# Chassis924.net
KiCad netlist of a schematic drawn in EasyEDA Pro
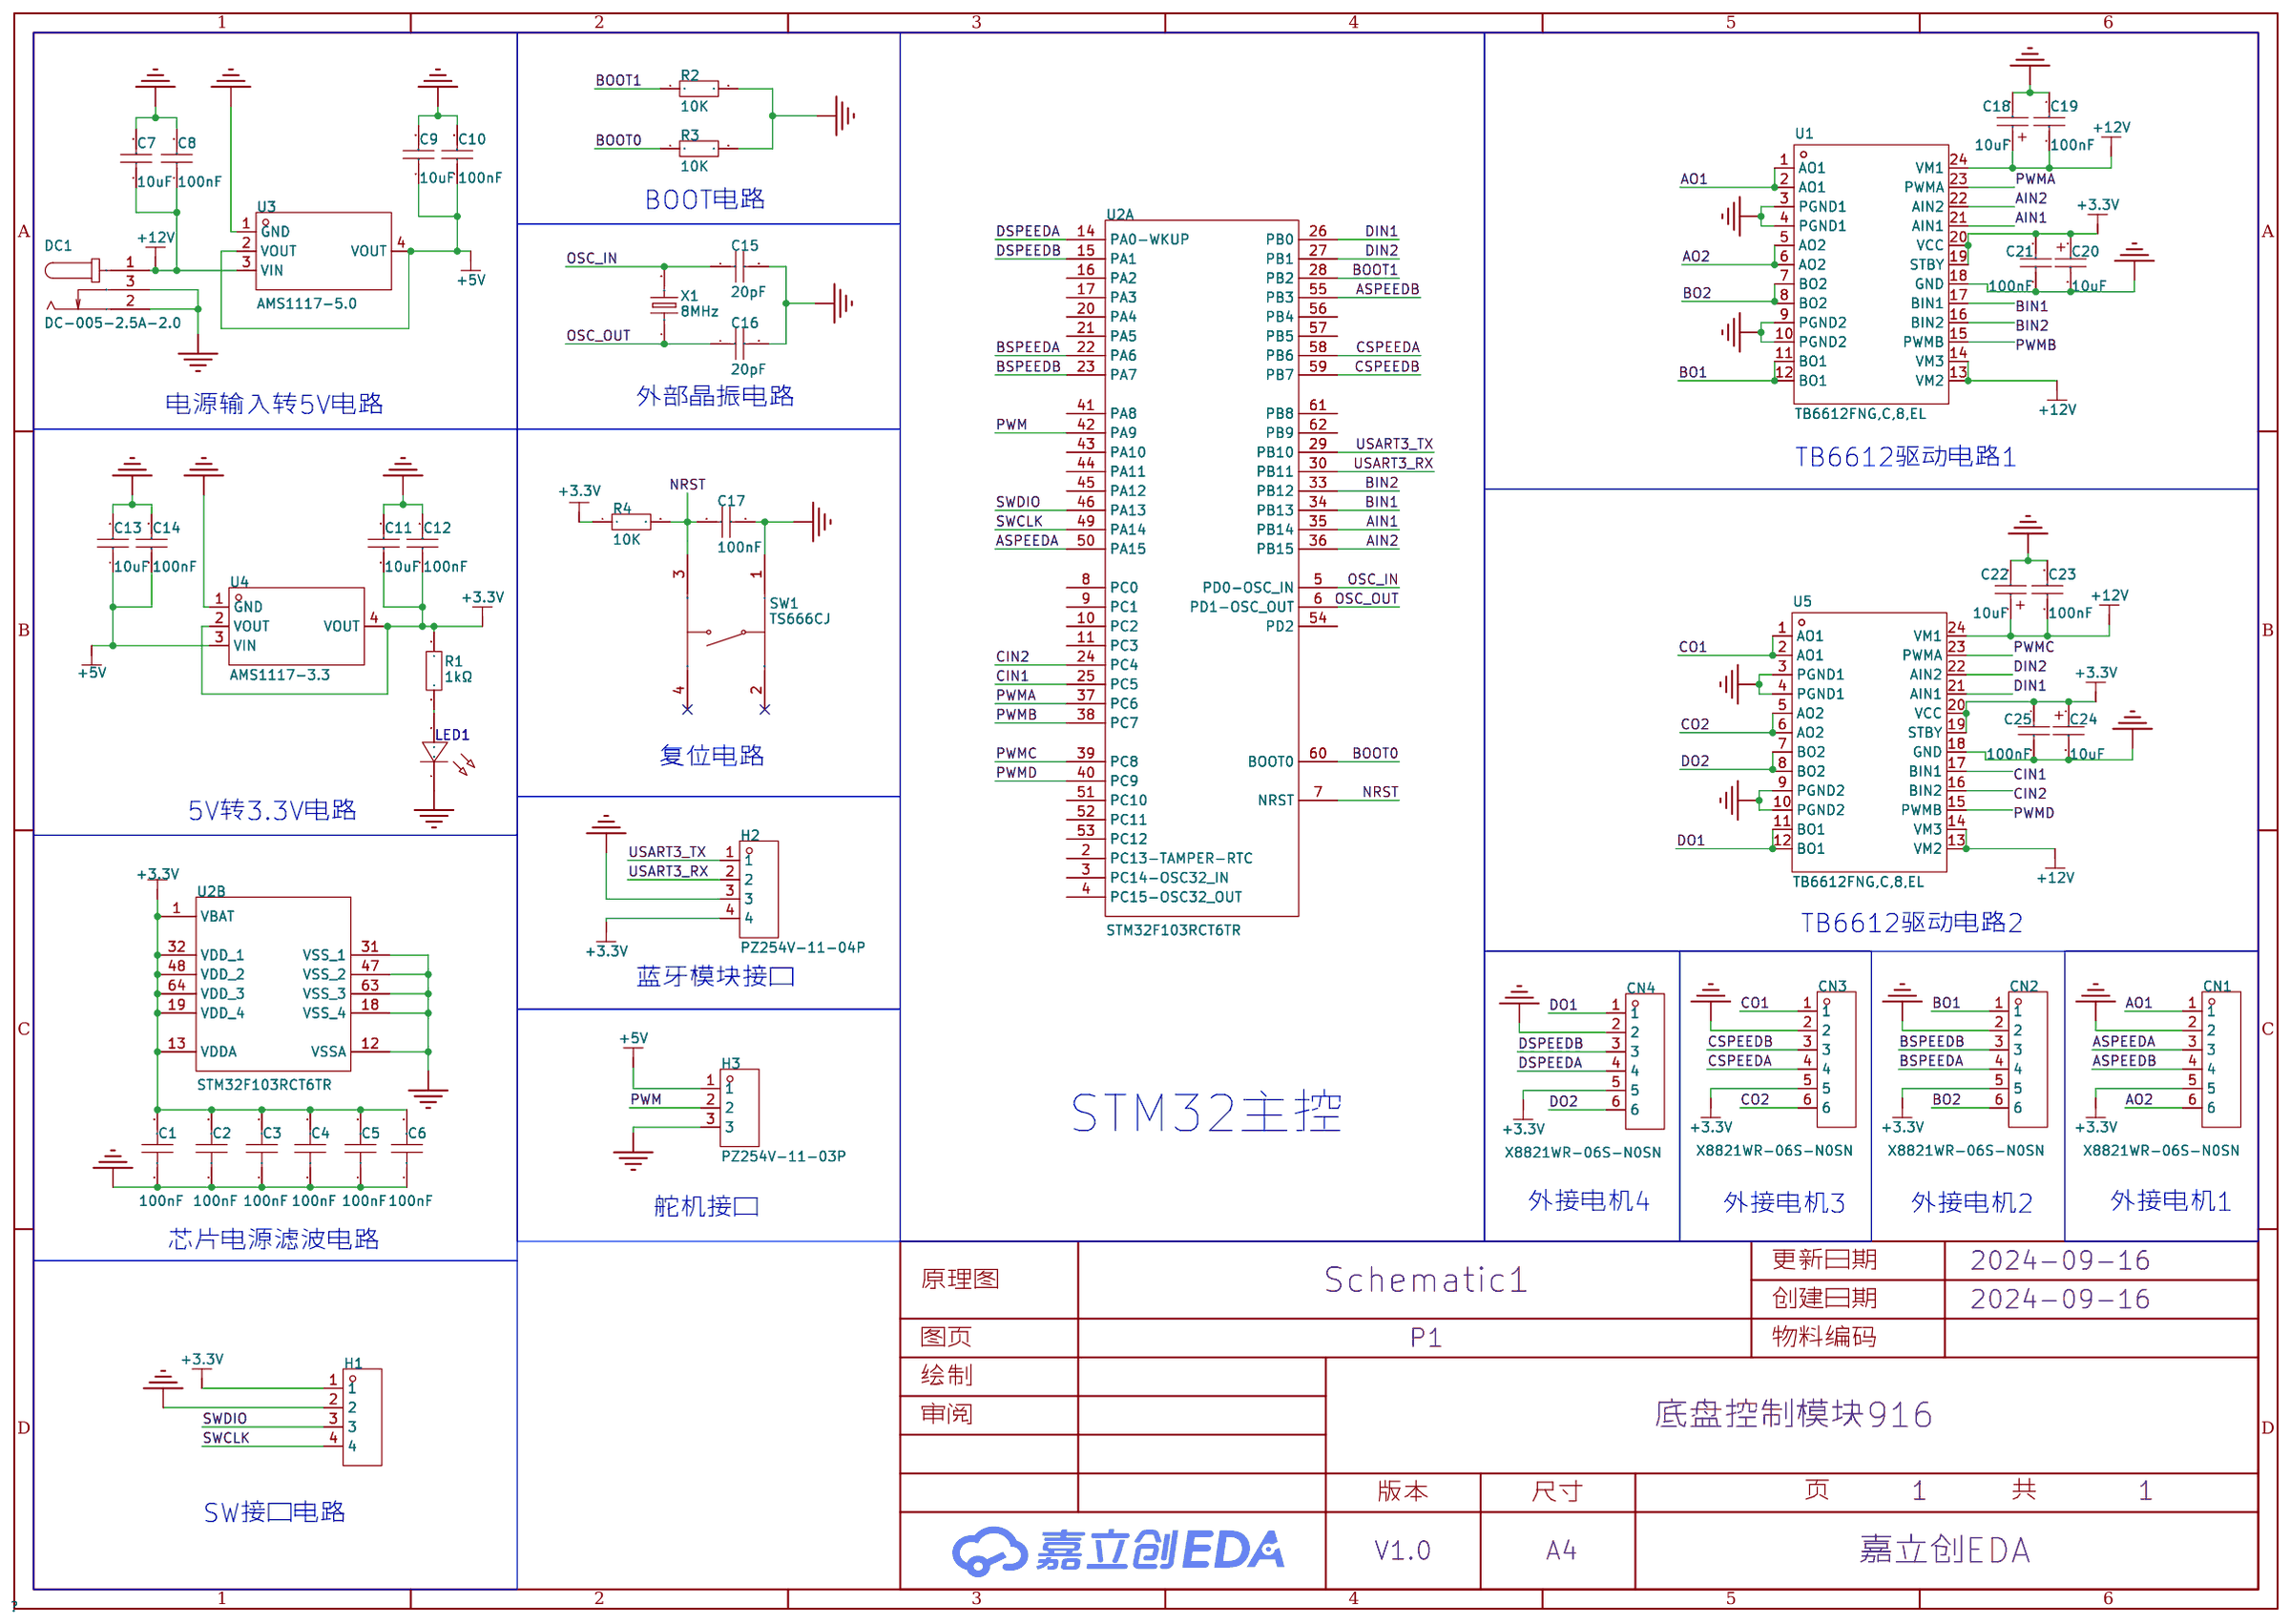
[diagram p0: schematic sheet]

(export (version "E")
  (design (tool "Eeschema 10.0.6"))
  (components
    (comp (ref "C1")
      (value "100nF")
      (footprint "easyedapro:C0603")
      (libsource (lib "easyedapro") (part "CapAcitance"))
    )
    (comp (ref "C2")
      (value "100nF")
      (footprint "easyedapro:C0603")
      (libsource (lib "easyedapro") (part "CapAcitance"))
    )
    (comp (ref "C3")
      (value "100nF")
      (footprint "easyedapro:C0603")
      (libsource (lib "easyedapro") (part "CapAcitance"))
    )
    (comp (ref "C4")
      (value "100nF")
      (footprint "easyedapro:C0603")
      (libsource (lib "easyedapro") (part "CapAcitance"))
    )
    (comp (ref "C5")
      (value "100nF")
      (footprint "easyedapro:C0603")
      (libsource (lib "easyedapro") (part "CapAcitance"))
    )
    (comp (ref "C6")
      (value "100nF")
      (footprint "easyedapro:C0603")
      (libsource (lib "easyedapro") (part "CapAcitance"))
    )
    (comp (ref "C7")
      (value "10uF")
      (footprint "easyedapro:C0402")
      (description "容值:10uF;精度:±20%;额定电压:6.3V;材质(温度系数):X5R;")
      (fields
        (field (name "Manufacturer Part") "CL05A106MQ5NUNC")
        (field (name "Manufacturer") "SAMSUNG(三星)")
      )
      (libsource (lib "easyedapro") (part "CL05A106MQ5NUNC"))
    )
    (comp (ref "C8")
      (value "100nF")
      (footprint "easyedapro:C0402")
      (description "容值:100nF;精度:±10%;额定电压:16V;材质(温度系数):X7R;")
      (fields
        (field (name "Manufacturer Part") "CL05B104KO5NNNC")
        (field (name "Manufacturer") "SAMSUNG(三星)")
      )
      (libsource (lib "easyedapro") (part "CL05B104KO5NNNC"))
    )
    (comp (ref "C9")
      (value "10uF")
      (footprint "easyedapro:C0402")
      (description "容值:10uF;精度:±20%;额定电压:6.3V;材质(温度系数):X5R;")
      (fields
        (field (name "Manufacturer Part") "CL05A106MQ5NUNC")
        (field (name "Manufacturer") "SAMSUNG(三星)")
      )
      (libsource (lib "easyedapro") (part "CL05A106MQ5NUNC"))
    )
    (comp (ref "C10")
      (value "100nF")
      (footprint "easyedapro:C0402")
      (description "容值:100nF;精度:±10%;额定电压:16V;材质(温度系数):X7R;")
      (fields
        (field (name "Manufacturer Part") "CL05B104KO5NNNC")
        (field (name "Manufacturer") "SAMSUNG(三星)")
      )
      (libsource (lib "easyedapro") (part "CL05B104KO5NNNC"))
    )
    (comp (ref "C11")
      (value "10uF")
      (footprint "easyedapro:C0402")
      (description "容值:10uF;精度:±20%;额定电压:6.3V;材质(温度系数):X5R;")
      (fields
        (field (name "Manufacturer Part") "CL05A106MQ5NUNC")
        (field (name "Manufacturer") "SAMSUNG(三星)")
      )
      (libsource (lib "easyedapro") (part "CL05A106MQ5NUNC"))
    )
    (comp (ref "C12")
      (value "100nF")
      (footprint "easyedapro:C0402")
      (description "容值:100nF;精度:±10%;额定电压:16V;材质(温度系数):X7R;")
      (fields
        (field (name "Manufacturer Part") "CL05B104KO5NNNC")
        (field (name "Manufacturer") "SAMSUNG(三星)")
      )
      (libsource (lib "easyedapro") (part "CL05B104KO5NNNC"))
    )
    (comp (ref "C13")
      (value "10uF")
      (footprint "easyedapro:C0402")
      (description "容值:10uF;精度:±20%;额定电压:6.3V;材质(温度系数):X5R;")
      (fields
        (field (name "Manufacturer Part") "CL05A106MQ5NUNC")
        (field (name "Manufacturer") "SAMSUNG(三星)")
      )
      (libsource (lib "easyedapro") (part "CL05A106MQ5NUNC"))
    )
    (comp (ref "C14")
      (value "100nF")
      (footprint "easyedapro:C0402")
      (description "容值:100nF;精度:±10%;额定电压:16V;材质(温度系数):X7R;")
      (fields
        (field (name "Manufacturer Part") "CL05B104KO5NNNC")
        (field (name "Manufacturer") "SAMSUNG(三星)")
      )
      (libsource (lib "easyedapro") (part "CL05B104KO5NNNC"))
    )
    (comp (ref "C15")
      (value "20pF")
      (footprint "easyedapro:C0402")
      (description "容值:20pF;精度:±5%;额定电压:50V;材质(温度系数):C0G;")
      (fields (field (name "Manufacturer Part") "0402CG200J500NT") (field (name "Manufacturer") "FH(风华)"))
      (libsource (lib "easyedapro") (part "0402CG200J500NT"))
    )
    (comp (ref "C16")
      (value "20pF")
      (footprint "easyedapro:C0402")
      (description "容值:20pF;精度:±5%;额定电压:50V;材质(温度系数):C0G;")
      (fields (field (name "Manufacturer Part") "0402CG200J500NT") (field (name "Manufacturer") "FH(风华)"))
      (libsource (lib "easyedapro") (part "0402CG200J500NT"))
    )
    (comp (ref "C17")
      (value "100nF")
      (footprint "easyedapro:C0402")
      (description "容值:100nF;精度:±10%;额定电压:16V;材质(温度系数):X7R;")
      (fields
        (field (name "Manufacturer Part") "CL05B104KO5NNNC")
        (field (name "Manufacturer") "SAMSUNG(三星)")
      )
      (libsource (lib "easyedapro") (part "CL05B104KO5NNNC"))
    )
    (comp (ref "C18")
      (value "10uF")
      (footprint "easyedapro:CAP-SMD_L3.2-W1.6-RD-C7171")
      (description "容值:10uF;精度:±10%;额定电压:16V;等效串联电阻:3Ω@100kHz;")
      (fields (field (name "Manufacturer Part") "TAJA106K016RNJ") (field (name "Manufacturer") "Kyocera AVX"))
      (libsource (lib "easyedapro") (part "TAJA106K016RNJ"))
    )
    (comp (ref "C19")
      (value "100nF")
      (footprint "easyedapro:C0402")
      (description "容值:100nF;精度:±10%;额定电压:16V;材质(温度系数):X7R;")
      (fields
        (field (name "Manufacturer Part") "CL05B104KO5NNNC")
        (field (name "Manufacturer") "SAMSUNG(三星)")
      )
      (libsource (lib "easyedapro") (part "CL05B104KO5NNNC"))
    )
    (comp (ref "C20")
      (value "10uF")
      (footprint "easyedapro:CAP-SMD_L3.2-W1.6-RD-C7171")
      (description "容值:10uF;精度:±10%;额定电压:16V;等效串联电阻:3Ω@100kHz;")
      (fields (field (name "Manufacturer Part") "TAJA106K016RNJ") (field (name "Manufacturer") "Kyocera AVX"))
      (libsource (lib "easyedapro") (part "TAJA106K016RNJ"))
    )
    (comp (ref "C21")
      (value "100nF")
      (footprint "easyedapro:C0402")
      (description "容值:100nF;精度:±10%;额定电压:16V;材质(温度系数):X7R;")
      (fields
        (field (name "Manufacturer Part") "CL05B104KO5NNNC")
        (field (name "Manufacturer") "SAMSUNG(三星)")
      )
      (libsource (lib "easyedapro") (part "CL05B104KO5NNNC"))
    )
    (comp (ref "C22")
      (value "10uF")
      (footprint "easyedapro:CAP-SMD_L3.2-W1.6-RD-C7171")
      (description "容值:10uF;精度:±10%;额定电压:16V;等效串联电阻:3Ω@100kHz;")
      (fields (field (name "Manufacturer Part") "TAJA106K016RNJ") (field (name "Manufacturer") "Kyocera AVX"))
      (libsource (lib "easyedapro") (part "TAJA106K016RNJ"))
    )
    (comp (ref "C23")
      (value "100nF")
      (footprint "easyedapro:C0402")
      (description "容值:100nF;精度:±10%;额定电压:16V;材质(温度系数):X7R;")
      (fields
        (field (name "Manufacturer Part") "CL05B104KO5NNNC")
        (field (name "Manufacturer") "SAMSUNG(三星)")
      )
      (libsource (lib "easyedapro") (part "CL05B104KO5NNNC"))
    )
    (comp (ref "C24")
      (value "10uF")
      (footprint "easyedapro:CAP-SMD_L3.2-W1.6-RD-C7171")
      (description "容值:10uF;精度:±10%;额定电压:16V;等效串联电阻:3Ω@100kHz;")
      (fields (field (name "Manufacturer Part") "TAJA106K016RNJ") (field (name "Manufacturer") "Kyocera AVX"))
      (libsource (lib "easyedapro") (part "TAJA106K016RNJ"))
    )
    (comp (ref "C25")
      (value "100nF")
      (footprint "easyedapro:C0402")
      (description "容值:100nF;精度:±10%;额定电压:16V;材质(温度系数):X7R;")
      (fields
        (field (name "Manufacturer Part") "CL05B104KO5NNNC")
        (field (name "Manufacturer") "SAMSUNG(三星)")
      )
      (libsource (lib "easyedapro") (part "CL05B104KO5NNNC"))
    )
    (comp (ref "CN1")
      (value "X8821WR-06S-N0SN")
      (footprint "easyedapro:CONN-TH_6P-P2.50_X8821WR-06S-N2SN")
      (description "插针结构:1x6P;间距:2.5mm;安装方式:弯插;参考系列:XH;总PIN数:6P;排数:1;每排PIN数:6;行距:-;额定电流:3A;触头材质:黄铜;触头镀层:锡;工作温度范围:-;")
      (fields (field (name "Manufacturer") "XKB Connection(中国星坤)"))
      (libsource (lib "easyedapro") (part "X8821WR-06S-N0SN"))
    )
    (comp (ref "CN2")
      (value "X8821WR-06S-N0SN")
      (footprint "easyedapro:CONN-TH_6P-P2.50_X8821WR-06S-N2SN")
      (description "插针结构:1x6P;间距:2.5mm;安装方式:弯插;参考系列:XH;总PIN数:6P;排数:1;每排PIN数:6;行距:-;额定电流:3A;触头材质:黄铜;触头镀层:锡;工作温度范围:-;")
      (fields (field (name "Manufacturer") "XKB Connection(中国星坤)"))
      (libsource (lib "easyedapro") (part "X8821WR-06S-N0SN"))
    )
    (comp (ref "CN3")
      (value "X8821WR-06S-N0SN")
      (footprint "easyedapro:CONN-TH_6P-P2.50_X8821WR-06S-N2SN")
      (description "插针结构:1x6P;间距:2.5mm;安装方式:弯插;参考系列:XH;总PIN数:6P;排数:1;每排PIN数:6;行距:-;额定电流:3A;触头材质:黄铜;触头镀层:锡;工作温度范围:-;")
      (fields (field (name "Manufacturer") "XKB Connection(中国星坤)"))
      (libsource (lib "easyedapro") (part "X8821WR-06S-N0SN"))
    )
    (comp (ref "CN4")
      (value "X8821WR-06S-N0SN")
      (footprint "easyedapro:CONN-TH_6P-P2.50_X8821WR-06S-N2SN")
      (description "插针结构:1x6P;间距:2.5mm;安装方式:弯插;参考系列:XH;总PIN数:6P;排数:1;每排PIN数:6;行距:-;额定电流:3A;触头材质:黄铜;触头镀层:锡;工作温度范围:-;")
      (fields (field (name "Manufacturer") "XKB Connection(中国星坤)"))
      (libsource (lib "easyedapro") (part "X8821WR-06S-N0SN"))
    )
    (comp (ref "DC1")
      (value "DC-005-2.5A-2.0")
      (footprint "easyedapro:CONN-TH_DC-005-2.5A-2.0")
      (fields (field (name "Manufacturer") "XKB Connection(中国星坤)"))
      (libsource (lib "easyedapro") (part "DC-005-2.5A-2.0"))
    )
    (comp (ref "H1")
      (value "~")
      (footprint "easyedapro:HDR-TH_4P-P2.54-V-M")
      (libsource (lib "easyedapro") (part "PZ254V-11-04P"))
    )
    (comp (ref "H2")
      (value "PZ254V-11-04P")
      (footprint "easyedapro:HDR-TH_4P-P2.54-V-M")
      (fields (field (name "Manufacturer") "XFCN(兴飞)"))
      (libsource (lib "easyedapro") (part "PZ254V-11-04P_C2691448"))
    )
    (comp (ref "H3")
      (value "PZ254V-11-03P")
      (footprint "easyedapro:HDR-TH_3P-P2.54-V-M")
      (fields (field (name "Manufacturer") "XFCN(兴飞)"))
      (libsource (lib "easyedapro") (part "PZ254V-11-03P_C2937625"))
    )
    (comp (ref "LED1")
      (value "~")
      (footprint "easyedapro:LED_0805")
      (libsource (lib "easyedapro") (part "LED_B"))
    )
    (comp (ref "R1")
      (value "1kΩ")
      (footprint "easyedapro:R0603")
      (description "电阻类型:厚膜电阻;阻值:1kΩ;精度:±1%;功率:100mW;最大工作电压:75V;温度系数:±100ppm/°C;")
      (fields
        (field (name "Manufacturer Part") "0603WAF1001T5E")
        (field (name "Manufacturer") "UNI-ROYAL(厚声)")
      )
      (libsource (lib "easyedapro") (part "0603WAF1001T5E"))
    )
    (comp (ref "R2") (value "10K") (footprint "easyedapro:R0603") (libsource (lib "easyedapro") (part "电阻")))
    (comp (ref "R3") (value "10K") (footprint "easyedapro:R0603") (libsource (lib "easyedapro") (part "电阻")))
    (comp (ref "R4") (value "10K") (footprint "easyedapro:R0603") (libsource (lib "easyedapro") (part "电阻")))
    (comp (ref "SW1")
      (value "TS666CJ")
      (footprint "easyedapro:SW-TH_4P-L6.0-W6.0-P4.50-LS6.5")
      (fields (field (name "Manufacturer") "SHOU HAN(首韩)"))
      (libsource (lib "easyedapro") (part "TS666CJ"))
    )
    (comp (ref "U1")
      (value "TB6612FNG,C,8,EL")
      (footprint "easyedapro:SSOP-24_L8.3-W5.6-P0.65-LS7.6-BL")
      (fields (field (name "Manufacturer") "TOSHIBA(东芝)"))
      (libsource (lib "easyedapro") (part "TB6612FNG,C,8,EL"))
    )
    (comp (ref "U2")
      (value "STM32F103RCT6TR")
      (footprint "easyedapro:LQFP-64_L10.0-W10.0-P0.50-LS12.0-BL")
      (description "CPU内核:ARM-M3;程序存储容量:256KB;RAM总容量:48KB;GPIO端口数量:51;工作电压范围:2V~3.6V;CPU最大主频:72MHz;程序存储器类型:FLASH;")
      (fields (field (name "Manufacturer") "ST(意法半导体)"))
      (libsource (lib "easyedapro") (part "STM32F103RCT6TR"))
    )
    (comp (ref "U3")
      (value "AMS1117-5.0")
      (footprint "easyedapro:SOT-223_L6.5-W3.5-P2.30-LS7.0-BR")
      (description "输出类型:固定;最大输入电压:12V;输出电压:5V;最大输出电流:1A;电源纹波抑制比(PSRR):68dB@(120Hz);输出极性:正极;")
      (fields (field (name "Manufacturer") "AMS"))
      (libsource (lib "easyedapro") (part "AMS1117-5.0"))
    )
    (comp (ref "U4")
      (value "AMS1117-3.3")
      (footprint "easyedapro:SOT-223-3_L6.5-W3.4-P2.30-LS7.0-BR")
      (description "输出类型:固定;最大输入电压:-;输出电压:3.3V;最大输出电流:1A;电源纹波抑制比(PSRR):72dB@(120Hz);输出极性:正极;")
      (fields (field (name "Manufacturer") "AMS"))
      (libsource (lib "easyedapro") (part "AMS1117-3.3"))
    )
    (comp (ref "U5")
      (value "TB6612FNG,C,8,EL")
      (footprint "easyedapro:SSOP-24_L8.3-W5.6-P0.65-LS7.6-BL")
      (fields (field (name "Manufacturer") "TOSHIBA(东芝)"))
      (libsource (lib "easyedapro") (part "TB6612FNG,C,8,EL"))
    )
    (comp (ref "X1")
      (value "8MHz")
      (footprint "easyedapro:HC-49US_L11.5-W4.5-P4.88")
      (description "晶振类型:直插晶振;频率:8MHz;常温频差:±20ppm;外接负载电容:20pF;频率稳定度(全温):±20ppm;")
      (fields
        (field (name "Manufacturer Part") "49S-8.000-20-20-20/A")
        (field (name "Manufacturer") "LIMING(利明)")
      )
      (libsource (lib "easyedapro") (part "49S-8.000-20-20-20/A"))
    )
  )
  (nets
    (net (code "1") (name "+3.3V") (class "Default")
      (node (ref "C1") (pin "2") (pinfunction "2_2") (pintype "input"))
      (node (ref "C11") (pin "1") (pinfunction "1_1") (pintype "input"))
      (node (ref "C12") (pin "1") (pinfunction "1_1") (pintype "input"))
      (node (ref "C2") (pin "2") (pinfunction "2_2") (pintype "input"))
      (node (ref "C20") (pin "1") (pinfunction "1_1") (pintype "input"))
      (node (ref "C21") (pin "1") (pinfunction "1_1") (pintype "input"))
      (node (ref "C24") (pin "1") (pinfunction "1_1") (pintype "input"))
      (node (ref "C25") (pin "1") (pinfunction "1_1") (pintype "input"))
      (node (ref "C3") (pin "2") (pinfunction "2_2") (pintype "input"))
      (node (ref "C4") (pin "2") (pinfunction "2_2") (pintype "input"))
      (node (ref "C5") (pin "2") (pinfunction "2_2") (pintype "input"))
      (node (ref "C6") (pin "2") (pinfunction "2_2") (pintype "input"))
      (node (ref "CN1") (pin "5") (pinfunction "5_5") (pintype "unspecified"))
      (node (ref "CN2") (pin "5") (pinfunction "5_5") (pintype "unspecified"))
      (node (ref "CN3") (pin "5") (pinfunction "5_5") (pintype "unspecified"))
      (node (ref "CN4") (pin "5") (pinfunction "5_5") (pintype "unspecified"))
      (node (ref "H1") (pin "1") (pinfunction "1_1") (pintype "unspecified"))
      (node (ref "H2") (pin "4") (pinfunction "4_4") (pintype "unspecified"))
      (node (ref "R1") (pin "1") (pinfunction "1_1") (pintype "input"))
      (node (ref "R4") (pin "1") (pinfunction "1_1") (pintype "input"))
      (node (ref "U1") (pin "19") (pinfunction "STBY_19") (pintype "unspecified"))
      (node (ref "U1") (pin "20") (pinfunction "VCC_20") (pintype "unspecified"))
      (node (ref "U2") (pin "1") (pinfunction "VBAT_1") (pintype "unspecified"))
      (node (ref "U2") (pin "13") (pinfunction "VDDA_13") (pintype "unspecified"))
      (node (ref "U2") (pin "19") (pinfunction "VDD_4_19") (pintype "unspecified"))
      (node (ref "U2") (pin "32") (pinfunction "VDD_1_32") (pintype "unspecified"))
      (node (ref "U2") (pin "48") (pinfunction "VDD_2_48") (pintype "unspecified"))
      (node (ref "U2") (pin "64") (pinfunction "VDD_3_64") (pintype "unspecified"))
      (node (ref "U4") (pin "2") (pinfunction "VOUT_2") (pintype "unspecified"))
      (node (ref "U4") (pin "4") (pinfunction "VOUT_4") (pintype "unspecified"))
      (node (ref "U5") (pin "19") (pinfunction "STBY_19") (pintype "unspecified"))
      (node (ref "U5") (pin "20") (pinfunction "VCC_20") (pintype "unspecified"))
    )
    (net (code "2") (name "+5V") (class "Default")
      (node (ref "C10") (pin "1") (pinfunction "1_1") (pintype "input"))
      (node (ref "C13") (pin "1") (pinfunction "1_1") (pintype "input"))
      (node (ref "C14") (pin "1") (pinfunction "1_1") (pintype "input"))
      (node (ref "C9") (pin "1") (pinfunction "1_1") (pintype "input"))
      (node (ref "H3") (pin "1") (pinfunction "1_1") (pintype "unspecified"))
      (node (ref "U3") (pin "2") (pinfunction "VOUT_2") (pintype "unspecified"))
      (node (ref "U3") (pin "4") (pinfunction "VOUT_4") (pintype "unspecified"))
      (node (ref "U4") (pin "3") (pinfunction "VIN_3") (pintype "unspecified"))
    )
    (net (code "3") (name "+12V") (class "Default")
      (node (ref "C18") (pin "1") (pinfunction "1_1") (pintype "input"))
      (node (ref "C19") (pin "1") (pinfunction "1_1") (pintype "input"))
      (node (ref "C22") (pin "1") (pinfunction "1_1") (pintype "input"))
      (node (ref "C23") (pin "1") (pinfunction "1_1") (pintype "input"))
      (node (ref "C7") (pin "1") (pinfunction "1_1") (pintype "input"))
      (node (ref "C8") (pin "1") (pinfunction "1_1") (pintype "input"))
      (node (ref "DC1") (pin "1") (pinfunction "1_1") (pintype "unspecified"))
      (node (ref "U1") (pin "13") (pinfunction "VM2_13") (pintype "unspecified"))
      (node (ref "U1") (pin "14") (pinfunction "VM3_14") (pintype "unspecified"))
      (node (ref "U1") (pin "24") (pinfunction "VM1_24") (pintype "unspecified"))
      (node (ref "U3") (pin "3") (pinfunction "VIN_3") (pintype "unspecified"))
      (node (ref "U5") (pin "13") (pinfunction "VM2_13") (pintype "unspecified"))
      (node (ref "U5") (pin "14") (pinfunction "VM3_14") (pintype "unspecified"))
      (node (ref "U5") (pin "24") (pinfunction "VM1_24") (pintype "unspecified"))
    )
    (net (code "4") (name "/AIN1") (class "Default")
      (node (ref "U1") (pin "21") (pinfunction "AIN1_21") (pintype "unspecified"))
      (node (ref "U2") (pin "35") (pinfunction "PB14_35") (pintype "bidirectional"))
    )
    (net (code "5") (name "/AIN2") (class "Default")
      (node (ref "U1") (pin "22") (pinfunction "AIN2_22") (pintype "unspecified"))
      (node (ref "U2") (pin "36") (pinfunction "PB15_36") (pintype "bidirectional"))
    )
    (net (code "6") (name "/AO1") (class "Default")
      (node (ref "CN1") (pin "1") (pinfunction "1_1") (pintype "unspecified"))
      (node (ref "U1") (pin "1") (pinfunction "AO1_1") (pintype "unspecified"))
      (node (ref "U1") (pin "2") (pinfunction "AO1_2") (pintype "unspecified"))
    )
    (net (code "7") (name "/AO2") (class "Default")
      (node (ref "CN1") (pin "6") (pinfunction "6_6") (pintype "unspecified"))
      (node (ref "U1") (pin "5") (pinfunction "AO2_5") (pintype "unspecified"))
      (node (ref "U1") (pin "6") (pinfunction "AO2_6") (pintype "unspecified"))
    )
    (net (code "8") (name "/ASPEEDA") (class "Default")
      (node (ref "CN1") (pin "3") (pinfunction "3_3") (pintype "unspecified"))
      (node (ref "U2") (pin "50") (pinfunction "PA15_50") (pintype "bidirectional"))
    )
    (net (code "9") (name "/ASPEEDB") (class "Default")
      (node (ref "CN1") (pin "4") (pinfunction "4_4") (pintype "unspecified"))
      (node (ref "U2") (pin "55") (pinfunction "PB3_55") (pintype "bidirectional"))
    )
    (net (code "10") (name "/BIN1") (class "Default")
      (node (ref "U1") (pin "17") (pinfunction "BIN1_17") (pintype "unspecified"))
      (node (ref "U2") (pin "34") (pinfunction "PB13_34") (pintype "bidirectional"))
    )
    (net (code "11") (name "/BIN2") (class "Default")
      (node (ref "U1") (pin "16") (pinfunction "BIN2_16") (pintype "unspecified"))
      (node (ref "U2") (pin "33") (pinfunction "PB12_33") (pintype "bidirectional"))
    )
    (net (code "12") (name "/BO1") (class "Default")
      (node (ref "CN2") (pin "1") (pinfunction "1_1") (pintype "unspecified"))
      (node (ref "U1") (pin "11") (pinfunction "BO1_11") (pintype "unspecified"))
      (node (ref "U1") (pin "12") (pinfunction "BO1_12") (pintype "unspecified"))
    )
    (net (code "13") (name "/BO2") (class "Default")
      (node (ref "CN2") (pin "6") (pinfunction "6_6") (pintype "unspecified"))
      (node (ref "U1") (pin "7") (pinfunction "BO2_7") (pintype "unspecified"))
      (node (ref "U1") (pin "8") (pinfunction "BO2_8") (pintype "unspecified"))
    )
    (net (code "14") (name "/BOOT0") (class "Default")
      (node (ref "R3") (pin "1") (pinfunction "1_1") (pintype "input"))
      (node (ref "U2") (pin "60") (pinfunction "BOOT0_60") (pintype "unspecified"))
    )
    (net (code "15") (name "/BOOT1") (class "Default")
      (node (ref "R2") (pin "1") (pinfunction "1_1") (pintype "input"))
      (node (ref "U2") (pin "28") (pinfunction "PB2_28") (pintype "bidirectional"))
    )
    (net (code "16") (name "/BSPEEDA") (class "Default")
      (node (ref "CN2") (pin "4") (pinfunction "4_4") (pintype "unspecified"))
      (node (ref "U2") (pin "22") (pinfunction "PA6_22") (pintype "bidirectional"))
    )
    (net (code "17") (name "/BSPEEDB") (class "Default")
      (node (ref "CN2") (pin "3") (pinfunction "3_3") (pintype "unspecified"))
      (node (ref "U2") (pin "23") (pinfunction "PA7_23") (pintype "bidirectional"))
    )
    (net (code "18") (name "/CIN1") (class "Default")
      (node (ref "U2") (pin "25") (pinfunction "PC5_25") (pintype "bidirectional"))
      (node (ref "U5") (pin "17") (pinfunction "BIN1_17") (pintype "unspecified"))
    )
    (net (code "19") (name "/CIN2") (class "Default")
      (node (ref "U2") (pin "24") (pinfunction "PC4_24") (pintype "bidirectional"))
      (node (ref "U5") (pin "16") (pinfunction "BIN2_16") (pintype "unspecified"))
    )
    (net (code "20") (name "/CO1") (class "Default")
      (node (ref "CN3") (pin "1") (pinfunction "1_1") (pintype "unspecified"))
      (node (ref "U5") (pin "1") (pinfunction "AO1_1") (pintype "unspecified"))
      (node (ref "U5") (pin "2") (pinfunction "AO1_2") (pintype "unspecified"))
    )
    (net (code "21") (name "/CO2") (class "Default")
      (node (ref "CN3") (pin "6") (pinfunction "6_6") (pintype "unspecified"))
      (node (ref "U5") (pin "5") (pinfunction "AO2_5") (pintype "unspecified"))
      (node (ref "U5") (pin "6") (pinfunction "AO2_6") (pintype "unspecified"))
    )
    (net (code "22") (name "/CSPEEDA") (class "Default")
      (node (ref "CN3") (pin "4") (pinfunction "4_4") (pintype "unspecified"))
      (node (ref "U2") (pin "58") (pinfunction "PB6_58") (pintype "bidirectional"))
    )
    (net (code "23") (name "/CSPEEDB") (class "Default")
      (node (ref "CN3") (pin "3") (pinfunction "3_3") (pintype "unspecified"))
      (node (ref "U2") (pin "59") (pinfunction "PB7_59") (pintype "bidirectional"))
    )
    (net (code "24") (name "/DIN1") (class "Default")
      (node (ref "U2") (pin "26") (pinfunction "PB0_26") (pintype "bidirectional"))
      (node (ref "U5") (pin "21") (pinfunction "AIN1_21") (pintype "unspecified"))
    )
    (net (code "25") (name "/DIN2") (class "Default")
      (node (ref "U2") (pin "27") (pinfunction "PB1_27") (pintype "bidirectional"))
      (node (ref "U5") (pin "22") (pinfunction "AIN2_22") (pintype "unspecified"))
    )
    (net (code "26") (name "/DO1") (class "Default")
      (node (ref "CN4") (pin "1") (pinfunction "1_1") (pintype "unspecified"))
      (node (ref "U5") (pin "11") (pinfunction "BO1_11") (pintype "unspecified"))
      (node (ref "U5") (pin "12") (pinfunction "BO1_12") (pintype "unspecified"))
    )
    (net (code "27") (name "/DO2") (class "Default")
      (node (ref "CN4") (pin "6") (pinfunction "6_6") (pintype "unspecified"))
      (node (ref "U5") (pin "7") (pinfunction "BO2_7") (pintype "unspecified"))
      (node (ref "U5") (pin "8") (pinfunction "BO2_8") (pintype "unspecified"))
    )
    (net (code "28") (name "/DSPEEDA") (class "Default")
      (node (ref "CN4") (pin "4") (pinfunction "4_4") (pintype "unspecified"))
      (node (ref "U2") (pin "14") (pinfunction "PA0-WKUP_14") (pintype "bidirectional"))
    )
    (net (code "29") (name "/DSPEEDB") (class "Default")
      (node (ref "CN4") (pin "3") (pinfunction "3_3") (pintype "unspecified"))
      (node (ref "U2") (pin "15") (pinfunction "PA1_15") (pintype "bidirectional"))
    )
    (net (code "30") (name "/NRST") (class "Default")
      (node (ref "C17") (pin "2") (pinfunction "2_2") (pintype "input"))
      (node (ref "R4") (pin "2") (pinfunction "2_2") (pintype "input"))
      (node (ref "SW1") (pin "3") (pinfunction "C_3") (pintype "input"))
      (node (ref "U2") (pin "7") (pinfunction "NRST_7") (pintype "bidirectional"))
    )
    (net (code "31") (name "/OSC_IN") (class "Default")
      (node (ref "C15") (pin "1") (pinfunction "1_1") (pintype "input"))
      (node (ref "U2") (pin "5") (pinfunction "PD0-OSC_IN_5") (pintype "bidirectional"))
      (node (ref "X1") (pin "2") (pinfunction "2_2") (pintype "input"))
    )
    (net (code "32") (name "/OSC_OUT") (class "Default")
      (node (ref "C16") (pin "1") (pinfunction "1_1") (pintype "input"))
      (node (ref "U2") (pin "6") (pinfunction "PD1-OSC_OUT_6") (pintype "bidirectional"))
      (node (ref "X1") (pin "1") (pinfunction "1_1") (pintype "input"))
    )
    (net (code "33") (name "/PWM") (class "Default")
      (node (ref "H3") (pin "2") (pinfunction "2_2") (pintype "unspecified"))
      (node (ref "U2") (pin "42") (pinfunction "PA9_42") (pintype "bidirectional"))
    )
    (net (code "34") (name "/PWMA") (class "Default")
      (node (ref "U1") (pin "23") (pinfunction "PWMA_23") (pintype "unspecified"))
      (node (ref "U2") (pin "37") (pinfunction "PC6_37") (pintype "bidirectional"))
    )
    (net (code "35") (name "/PWMB") (class "Default")
      (node (ref "U1") (pin "15") (pinfunction "PWMB_15") (pintype "unspecified"))
      (node (ref "U2") (pin "38") (pinfunction "PC7_38") (pintype "bidirectional"))
    )
    (net (code "36") (name "/PWMC") (class "Default")
      (node (ref "U2") (pin "39") (pinfunction "PC8_39") (pintype "bidirectional"))
      (node (ref "U5") (pin "23") (pinfunction "PWMA_23") (pintype "unspecified"))
    )
    (net (code "37") (name "/PWMD") (class "Default")
      (node (ref "U2") (pin "40") (pinfunction "PC9_40") (pintype "bidirectional"))
      (node (ref "U5") (pin "15") (pinfunction "PWMB_15") (pintype "unspecified"))
    )
    (net (code "38") (name "/SWCLK") (class "Default")
      (node (ref "H1") (pin "4") (pinfunction "4_4") (pintype "unspecified"))
      (node (ref "U2") (pin "49") (pinfunction "PA14_49") (pintype "bidirectional"))
    )
    (net (code "39") (name "/SWDIO") (class "Default")
      (node (ref "H1") (pin "3") (pinfunction "3_3") (pintype "unspecified"))
      (node (ref "U2") (pin "46") (pinfunction "PA13_46") (pintype "bidirectional"))
    )
    (net (code "40") (name "/USART3_RX") (class "Default")
      (node (ref "H2") (pin "2") (pinfunction "2_2") (pintype "unspecified"))
      (node (ref "U2") (pin "30") (pinfunction "PB11_30") (pintype "bidirectional"))
    )
    (net (code "41") (name "/USART3_TX") (class "Default")
      (node (ref "H2") (pin "1") (pinfunction "1_1") (pintype "unspecified"))
      (node (ref "U2") (pin "29") (pinfunction "PB10_29") (pintype "bidirectional"))
    )
    (net (code "42") (name "GND") (class "Default")
      (node (ref "C1") (pin "1") (pinfunction "1_1") (pintype "input"))
      (node (ref "C10") (pin "2") (pinfunction "2_2") (pintype "input"))
      (node (ref "C11") (pin "2") (pinfunction "2_2") (pintype "input"))
      (node (ref "C12") (pin "2") (pinfunction "2_2") (pintype "input"))
      (node (ref "C13") (pin "2") (pinfunction "2_2") (pintype "input"))
      (node (ref "C14") (pin "2") (pinfunction "2_2") (pintype "input"))
      (node (ref "C15") (pin "2") (pinfunction "2_2") (pintype "input"))
      (node (ref "C16") (pin "2") (pinfunction "2_2") (pintype "input"))
      (node (ref "C17") (pin "1") (pinfunction "1_1") (pintype "input"))
      (node (ref "C18") (pin "2") (pinfunction "2_2") (pintype "input"))
      (node (ref "C19") (pin "2") (pinfunction "2_2") (pintype "input"))
      (node (ref "C2") (pin "1") (pinfunction "1_1") (pintype "input"))
      (node (ref "C20") (pin "2") (pinfunction "2_2") (pintype "input"))
      (node (ref "C21") (pin "2") (pinfunction "2_2") (pintype "input"))
      (node (ref "C22") (pin "2") (pinfunction "2_2") (pintype "input"))
      (node (ref "C23") (pin "2") (pinfunction "2_2") (pintype "input"))
      (node (ref "C24") (pin "2") (pinfunction "2_2") (pintype "input"))
      (node (ref "C25") (pin "2") (pinfunction "2_2") (pintype "input"))
      (node (ref "C3") (pin "1") (pinfunction "1_1") (pintype "input"))
      (node (ref "C4") (pin "1") (pinfunction "1_1") (pintype "input"))
      (node (ref "C5") (pin "1") (pinfunction "1_1") (pintype "input"))
      (node (ref "C6") (pin "1") (pinfunction "1_1") (pintype "input"))
      (node (ref "C7") (pin "2") (pinfunction "2_2") (pintype "input"))
      (node (ref "C8") (pin "2") (pinfunction "2_2") (pintype "input"))
      (node (ref "C9") (pin "2") (pinfunction "2_2") (pintype "input"))
      (node (ref "CN1") (pin "2") (pinfunction "2_2") (pintype "unspecified"))
      (node (ref "CN2") (pin "2") (pinfunction "2_2") (pintype "unspecified"))
      (node (ref "CN3") (pin "2") (pinfunction "2_2") (pintype "unspecified"))
      (node (ref "CN4") (pin "2") (pinfunction "2_2") (pintype "unspecified"))
      (node (ref "DC1") (pin "2") (pinfunction "2_2") (pintype "unspecified"))
      (node (ref "DC1") (pin "3") (pinfunction "3_3") (pintype "unspecified"))
      (node (ref "H1") (pin "2") (pinfunction "2_2") (pintype "unspecified"))
      (node (ref "H2") (pin "3") (pinfunction "3_3") (pintype "unspecified"))
      (node (ref "H3") (pin "3") (pinfunction "3_3") (pintype "unspecified"))
      (node (ref "LED1") (pin "1") (pinfunction "C_1") (pintype "input"))
      (node (ref "R2") (pin "2") (pinfunction "2_2") (pintype "input"))
      (node (ref "R3") (pin "2") (pinfunction "2_2") (pintype "input"))
      (node (ref "SW1") (pin "1") (pinfunction "A_1") (pintype "input"))
      (node (ref "U1") (pin "10") (pinfunction "PGND2_10") (pintype "unspecified"))
      (node (ref "U1") (pin "18") (pinfunction "GND_18") (pintype "unspecified"))
      (node (ref "U1") (pin "3") (pinfunction "PGND1_3") (pintype "unspecified"))
      (node (ref "U1") (pin "4") (pinfunction "PGND1_4") (pintype "unspecified"))
      (node (ref "U1") (pin "9") (pinfunction "PGND2_9") (pintype "unspecified"))
      (node (ref "U2") (pin "12") (pinfunction "VSSA_12") (pintype "unspecified"))
      (node (ref "U2") (pin "18") (pinfunction "VSS_4_18") (pintype "unspecified"))
      (node (ref "U2") (pin "31") (pinfunction "VSS_1_31") (pintype "unspecified"))
      (node (ref "U2") (pin "47") (pinfunction "VSS_2_47") (pintype "unspecified"))
      (node (ref "U2") (pin "63") (pinfunction "VSS_3_63") (pintype "unspecified"))
      (node (ref "U3") (pin "1") (pinfunction "GND_1") (pintype "unspecified"))
      (node (ref "U4") (pin "1") (pinfunction "GND_1") (pintype "unspecified"))
      (node (ref "U5") (pin "10") (pinfunction "PGND2_10") (pintype "unspecified"))
      (node (ref "U5") (pin "18") (pinfunction "GND_18") (pintype "unspecified"))
      (node (ref "U5") (pin "3") (pinfunction "PGND1_3") (pintype "unspecified"))
      (node (ref "U5") (pin "4") (pinfunction "PGND1_4") (pintype "unspecified"))
      (node (ref "U5") (pin "9") (pinfunction "PGND2_9") (pintype "unspecified"))
    )
    (net (code "43") (name "Net-(LED1-A)") (class "Default")
      (node (ref "LED1") (pin "2") (pinfunction "A_2") (pintype "input"))
      (node (ref "R1") (pin "2") (pinfunction "2_2") (pintype "input"))
    )
    (net (code "44") (name "unconnected-(SW1-B-Pad2)") (class "Default")
      (node (ref "SW1") (pin "2") (pinfunction "B_2") (pintype "input+no_connect"))
    )
    (net (code "45") (name "unconnected-(SW1-D-Pad4)") (class "Default")
      (node (ref "SW1") (pin "4") (pinfunction "D_4") (pintype "input+no_connect"))
    )
    (net (code "46") (name "unconnected-(U2A-PA2-Pad16)") (class "Default")
      (node (ref "U2") (pin "16") (pinfunction "PA2_16") (pintype "bidirectional"))
    )
    (net (code "47") (name "unconnected-(U2A-PA3-Pad17)") (class "Default")
      (node (ref "U2") (pin "17") (pinfunction "PA3_17") (pintype "bidirectional"))
    )
    (net (code "48") (name "unconnected-(U2A-PA4-Pad20)") (class "Default")
      (node (ref "U2") (pin "20") (pinfunction "PA4_20") (pintype "bidirectional"))
    )
    (net (code "49") (name "unconnected-(U2A-PA5-Pad21)") (class "Default")
      (node (ref "U2") (pin "21") (pinfunction "PA5_21") (pintype "bidirectional"))
    )
    (net (code "50") (name "unconnected-(U2A-PA8-Pad41)") (class "Default")
      (node (ref "U2") (pin "41") (pinfunction "PA8_41") (pintype "bidirectional"))
    )
    (net (code "51") (name "unconnected-(U2A-PA10-Pad43)") (class "Default")
      (node (ref "U2") (pin "43") (pinfunction "PA10_43") (pintype "bidirectional"))
    )
    (net (code "52") (name "unconnected-(U2A-PA11-Pad44)") (class "Default")
      (node (ref "U2") (pin "44") (pinfunction "PA11_44") (pintype "bidirectional"))
    )
    (net (code "53") (name "unconnected-(U2A-PA12-Pad45)") (class "Default")
      (node (ref "U2") (pin "45") (pinfunction "PA12_45") (pintype "bidirectional"))
    )
    (net (code "54") (name "unconnected-(U2A-PB4-Pad56)") (class "Default")
      (node (ref "U2") (pin "56") (pinfunction "PB4_56") (pintype "bidirectional"))
    )
    (net (code "55") (name "unconnected-(U2A-PB5-Pad57)") (class "Default")
      (node (ref "U2") (pin "57") (pinfunction "PB5_57") (pintype "bidirectional"))
    )
    (net (code "56") (name "unconnected-(U2A-PB8-Pad61)") (class "Default")
      (node (ref "U2") (pin "61") (pinfunction "PB8_61") (pintype "bidirectional"))
    )
    (net (code "57") (name "unconnected-(U2A-PB9-Pad62)") (class "Default")
      (node (ref "U2") (pin "62") (pinfunction "PB9_62") (pintype "bidirectional"))
    )
    (net (code "58") (name "unconnected-(U2A-PC0-Pad8)") (class "Default")
      (node (ref "U2") (pin "8") (pinfunction "PC0_8") (pintype "bidirectional"))
    )
    (net (code "59") (name "unconnected-(U2A-PC1-Pad9)") (class "Default")
      (node (ref "U2") (pin "9") (pinfunction "PC1_9") (pintype "bidirectional"))
    )
    (net (code "60") (name "unconnected-(U2A-PC2-Pad10)") (class "Default")
      (node (ref "U2") (pin "10") (pinfunction "PC2_10") (pintype "bidirectional"))
    )
    (net (code "61") (name "unconnected-(U2A-PC3-Pad11)") (class "Default")
      (node (ref "U2") (pin "11") (pinfunction "PC3_11") (pintype "bidirectional"))
    )
    (net (code "62") (name "unconnected-(U2A-PC10-Pad51)") (class "Default")
      (node (ref "U2") (pin "51") (pinfunction "PC10_51") (pintype "bidirectional"))
    )
    (net (code "63") (name "unconnected-(U2A-PC11-Pad52)") (class "Default")
      (node (ref "U2") (pin "52") (pinfunction "PC11_52") (pintype "bidirectional"))
    )
    (net (code "64") (name "unconnected-(U2A-PC12-Pad53)") (class "Default")
      (node (ref "U2") (pin "53") (pinfunction "PC12_53") (pintype "bidirectional"))
    )
    (net (code "65") (name "unconnected-(U2A-PC13-TAMPER-RTC-Pad2)") (class "Default")
      (node (ref "U2") (pin "2") (pinfunction "PC13-TAMPER-RTC_2") (pintype "bidirectional"))
    )
    (net (code "66") (name "unconnected-(U2A-PC14-OSC32_IN-Pad3)") (class "Default")
      (node (ref "U2") (pin "3") (pinfunction "PC14-OSC32_IN_3") (pintype "bidirectional"))
    )
    (net (code "67") (name "unconnected-(U2A-PC15-OSC32_OUT-Pad4)") (class "Default")
      (node (ref "U2") (pin "4") (pinfunction "PC15-OSC32_OUT_4") (pintype "bidirectional"))
    )
    (net (code "68") (name "unconnected-(U2A-PD2-Pad54)") (class "Default")
      (node (ref "U2") (pin "54") (pinfunction "PD2_54") (pintype "bidirectional"))
    )
  )
)
